# RiskChemi_Monitor_V1_03.net
KiCad netlist of a schematic drawn in Altium Designer
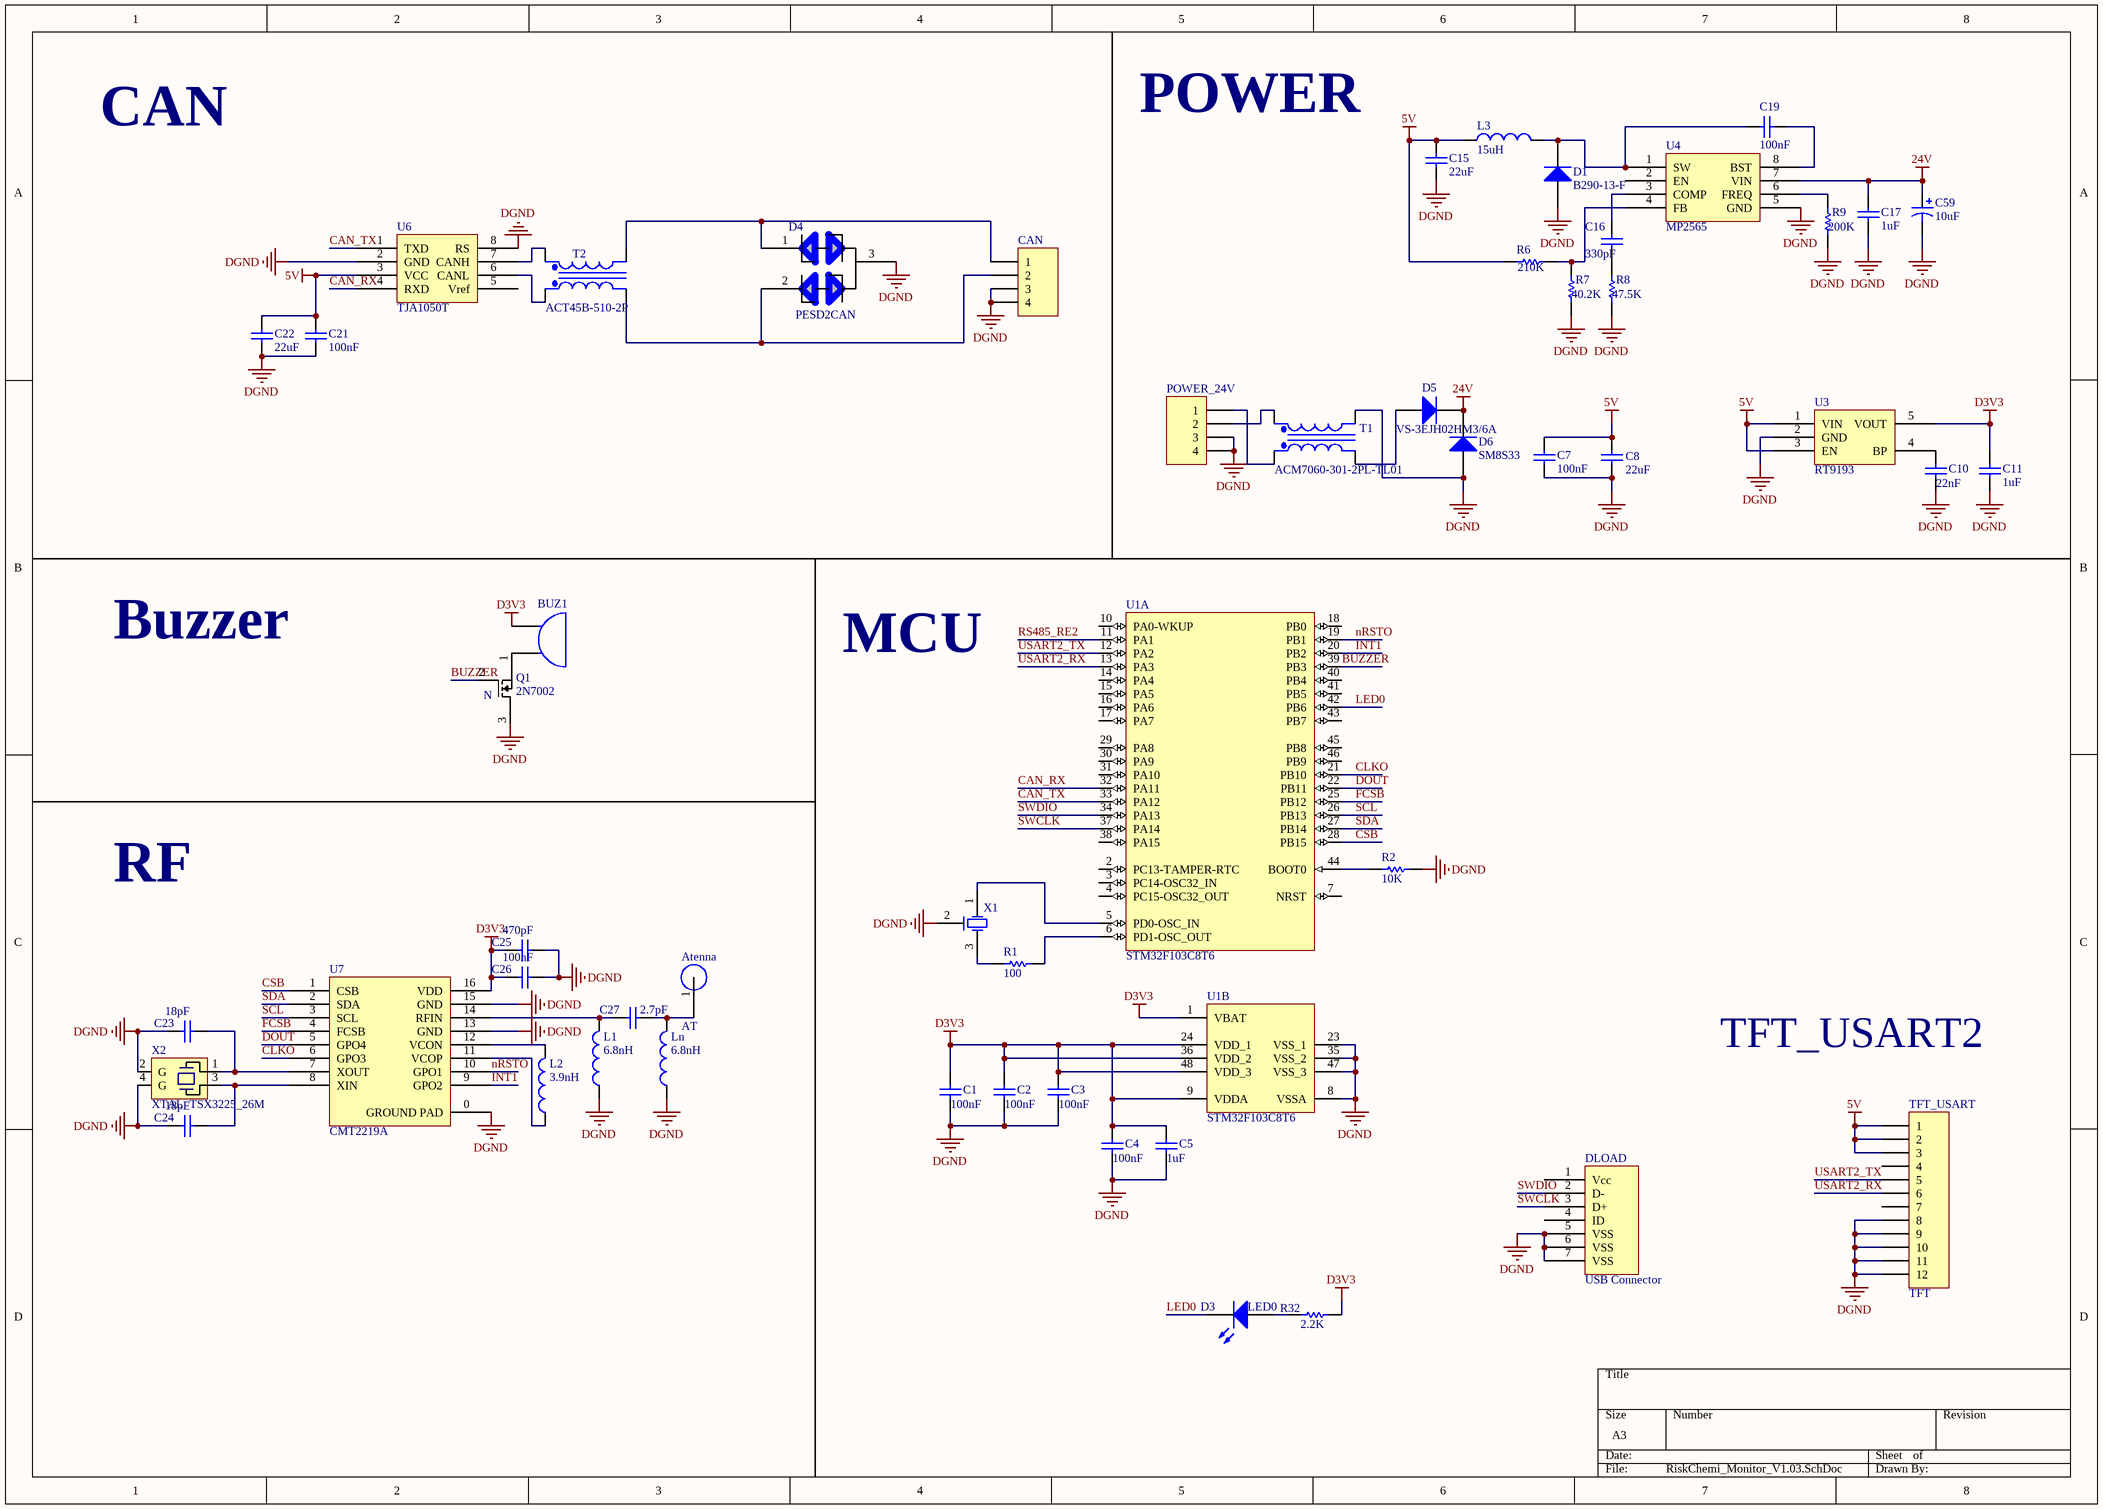
[diagram p0: RiskChemi_Monitor_V1.03.SchDoc]

(export (version "E")
  (design (tool "Eeschema 10.0.6"))
  (components
    (comp (ref "Atenna") (value "AT") (footprint "433MHz Atenna") (libsource (lib "MySchlib1") (part "AT")))
    (comp (ref "BUZ1")
      (value "BUZZER")
      (footprint "BUZ0905")
      (description "Buzzer")
      (libsource (lib "杂元件库") (part "BUZZER"))
    )
    (comp (ref "C1")
      (value "100nF")
      (footprint "0603")
      (description "Capacitor")
      (fields (field (name "PUBLISHER") "Altium Limited"))
      (libsource (lib "Miscellaneous Devices") (part "Cap"))
    )
    (comp (ref "C2")
      (value "100nF")
      (footprint "0603")
      (description "Capacitor")
      (fields (field (name "PUBLISHER") "Altium Limited"))
      (libsource (lib "Miscellaneous Devices") (part "Cap"))
    )
    (comp (ref "C3")
      (value "100nF")
      (footprint "0603")
      (description "Capacitor")
      (fields (field (name "PUBLISHER") "Altium Limited"))
      (libsource (lib "Miscellaneous Devices") (part "Cap"))
    )
    (comp (ref "C4")
      (value "100nF")
      (footprint "0603")
      (description "Capacitor")
      (fields (field (name "PUBLISHER") "Altium Limited"))
      (libsource (lib "Miscellaneous Devices") (part "Cap"))
    )
    (comp (ref "C5")
      (value "1uF")
      (footprint "0603")
      (description "Capacitor")
      (fields (field (name "PUBLISHER") "Altium Limited"))
      (libsource (lib "Miscellaneous Devices") (part "Cap"))
    )
    (comp (ref "C7")
      (value "100nF")
      (footprint "0805")
      (description "Capacitor,100V")
      (fields (field (name "PUBLISHER") "Altium Limited"))
      (libsource (lib "Miscellaneous Devices") (part "Cap"))
    )
    (comp (ref "C8")
      (value "22uF")
      (footprint "0805")
      (description "Capacitor")
      (fields (field (name "PUBLISHER") "Altium Limited"))
      (libsource (lib "Miscellaneous Devices") (part "Cap"))
    )
    (comp (ref "C10")
      (value "22nF")
      (footprint "BinFeng:0603")
      (description "Capacitor")
      (fields (field (name "PUBLISHER") "Altium Limited"))
      (libsource (lib "Miscellaneous Devices") (part "Cap"))
    )
    (comp (ref "C11")
      (value "1uF")
      (footprint "BinFeng:0603")
      (description "Capacitor")
      (fields (field (name "PUBLISHER") "Altium Limited"))
      (libsource (lib "Miscellaneous Devices") (part "Cap"))
    )
    (comp (ref "C15")
      (value "22uF")
      (footprint "0805")
      (description "Capacitor,50V")
      (fields (field (name "PUBLISHER") "Altium Limited"))
      (libsource (lib "Miscellaneous Devices") (part "Cap"))
    )
    (comp (ref "C16")
      (value "330pF")
      (footprint "BinFeng:0402")
      (description "Capacitor")
      (fields (field (name "PUBLISHER") "Altium Limited"))
      (libsource (lib "Miscellaneous Devices") (part "Cap"))
    )
    (comp (ref "C17")
      (value "1uF")
      (footprint "0805")
      (description "Capacitor,100V")
      (fields (field (name "PUBLISHER") "Altium Limited"))
      (libsource (lib "Miscellaneous Devices") (part "Cap"))
    )
    (comp (ref "C19")
      (value "100nF")
      (footprint "BinFeng:0402")
      (description "Capacitor")
      (fields (field (name "PUBLISHER") "Altium Limited"))
      (libsource (lib "Miscellaneous Devices") (part "Cap"))
    )
    (comp (ref "C21")
      (value "100nF")
      (footprint "0603")
      (description "Capacitor")
      (fields (field (name "PUBLISHER") "Altium Limited"))
      (libsource (lib "Miscellaneous Devices") (part "Cap"))
    )
    (comp (ref "C22")
      (value "22uF")
      (footprint "0805")
      (description "Capacitor")
      (fields (field (name "PUBLISHER") "Altium Limited"))
      (libsource (lib "Miscellaneous Devices") (part "Cap"))
    )
    (comp (ref "C23")
      (value "18pF")
      (footprint "BinFeng:0402")
      (description "Capacitor")
      (fields (field (name "PUBLISHER") "Altium Limited"))
      (libsource (lib "Miscellaneous Devices") (part "Cap"))
    )
    (comp (ref "C24")
      (value "18pF")
      (footprint "BinFeng:0402")
      (description "Capacitor")
      (fields (field (name "PUBLISHER") "Altium Limited"))
      (libsource (lib "Miscellaneous Devices") (part "Cap"))
    )
    (comp (ref "C25")
      (value "470pF")
      (footprint "BinFeng:0402")
      (description "Capacitor")
      (fields (field (name "PUBLISHER") "Altium Limited"))
      (libsource (lib "Miscellaneous Devices") (part "Cap"))
    )
    (comp (ref "C26")
      (value "100nF")
      (footprint "BinFeng:0603")
      (description "Capacitor")
      (fields (field (name "PUBLISHER") "Altium Limited"))
      (libsource (lib "Miscellaneous Devices") (part "Cap"))
    )
    (comp (ref "C27")
      (value "2.7pF")
      (footprint "BinFeng:nosilk_0402")
      (description "Capacitor")
      (fields (field (name "PUBLISHER") "Altium Limited"))
      (libsource (lib "Miscellaneous Devices") (part "Cap"))
    )
    (comp (ref "C59")
      (value "10uF")
      (footprint "6032_pol")
      (description "Polarized Capacitor (Radial)")
      (fields (field (name "PUBLISHER") "Altium Limited"))
      (libsource (lib "Miscellaneous Devices") (part "Cap Pol1"))
    )
    (comp (ref "CAN")
      (value "Header 4")
      (footprint "C3000VS")
      (description "Header, 4-Pin")
      (fields (field (name "PUBLISHER") "Altium Limited"))
      (libsource (lib "Miscellaneous Connectors") (part "Header 4"))
    )
    (comp (ref "D1")
      (value "B290-13-F")
      (footprint "back:B290")
      (description "Default Diode")
      (fields (field (name "PUBLISHER") "Altium Limited"))
      (libsource (lib "Miscellaneous Devices") (part "Diode"))
    )
    (comp (ref "D3")
      (value "LED0")
      (footprint "LED")
      (description "green LED")
      (fields (field (name "PUBLISHER") "Altium Limited"))
      (libsource (lib "Miscellaneous Devices") (part "LED0"))
    )
    (comp (ref "D4")
      (value "PESD2CAN")
      (footprint "SOT23")
      (libsource (lib "BinFeng_Connectors") (part "PESD1CAN"))
    )
    (comp (ref "D5")
      (value "VS-3EJH02HM3/6A")
      (footprint "back:B290")
      (description "1 Amp General Purpose Rectifier")
      (fields (field (name "PUBLISHER") "Altium Limited"))
      (libsource (lib "Miscellaneous Devices") (part "Diode 1N4007"))
    )
    (comp (ref "D6")
      (value "SM8S33")
      (footprint "SM8S")
      (description "1 Amp General Purpose Rectifier")
      (fields (field (name "PUBLISHER") "Altium Limited"))
      (libsource (lib "Miscellaneous Devices") (part "Diode 1N4007"))
    )
    (comp (ref "DLOAD")
      (value "USB Connector")
      (footprint "Mini_USB")
      (libsource (lib "BinFeng_Connectors") (part "Component_1"))
    )
    (comp (ref "L1")
      (value "6.8nH")
      (footprint "Miscellaneous Devices:0402")
      (description "Inductor")
      (fields (field (name "PUBLISHER") "Altium Limited"))
      (libsource (lib "Miscellaneous Devices") (part "Inductor"))
    )
    (comp (ref "L2")
      (value "3.9nH")
      (footprint "BinFeng:0603")
      (description "Inductor")
      (fields (field (name "PUBLISHER") "Altium Limited"))
      (libsource (lib "Miscellaneous Devices") (part "Inductor"))
    )
    (comp (ref "L3")
      (value "15uH")
      (footprint "4*4 Inductor")
      (description "Inductor, 1A")
      (fields (field (name "PUBLISHER") "Altium Limited"))
      (libsource (lib "Miscellaneous Devices") (part "Inductor"))
    )
    (comp (ref "Ln")
      (value "6.8nH")
      (footprint "Miscellaneous Devices:0402")
      (description "Inductor")
      (fields (field (name "PUBLISHER") "Altium Limited"))
      (libsource (lib "Miscellaneous Devices") (part "Inductor"))
    )
    (comp (ref "POWER_24V")
      (value "Header 4")
      (footprint "C3000VS")
      (description "Header, 4-Pin")
      (fields (field (name "PUBLISHER") "Altium Limited"))
      (libsource (lib "") (part "Header 4_1"))
    )
    (comp (ref "Q1") (value "2N7002") (footprint "2N7002") (libsource (lib "seeder") (part "N-MOSFET")))
    (comp (ref "R1")
      (value "100")
      (footprint "back:0603")
      (description "Resistor")
      (fields (field (name "PUBLISHER") "Altium Limited"))
      (libsource (lib "Miscellaneous Devices") (part "Res1"))
    )
    (comp (ref "R2")
      (value "10K")
      (footprint "back:0603")
      (description "Resistor")
      (fields (field (name "PUBLISHER") "Altium Limited"))
      (libsource (lib "Miscellaneous Devices") (part "Res1"))
    )
    (comp (ref "R6")
      (value "210K")
      (footprint "BinFeng:0402")
      (description "Resistor")
      (fields (field (name "PUBLISHER") "Altium Limited"))
      (libsource (lib "Miscellaneous Devices") (part "Res1"))
    )
    (comp (ref "R7")
      (value "40.2K")
      (footprint "BinFeng:0402")
      (description "Resistor")
      (fields (field (name "PUBLISHER") "Altium Limited"))
      (libsource (lib "Miscellaneous Devices") (part "Res1"))
    )
    (comp (ref "R8")
      (value "47.5K")
      (footprint "BinFeng:0402")
      (description "Resistor")
      (fields (field (name "PUBLISHER") "Altium Limited"))
      (libsource (lib "Miscellaneous Devices") (part "Res1"))
    )
    (comp (ref "R9")
      (value "200K")
      (footprint "BinFeng:0402")
      (description "Resistor")
      (fields (field (name "PUBLISHER") "Altium Limited"))
      (libsource (lib "Miscellaneous Devices") (part "Res1"))
    )
    (comp (ref "R32")
      (value "2.2K")
      (footprint "BinFeng:0603")
      (description "Resistor")
      (fields (field (name "PUBLISHER") "Altium Limited"))
      (libsource (lib "Miscellaneous Devices") (part "Res1"))
    )
    (comp (ref "T1")
      (value "ACM7060-301-2PL-TL01")
      (footprint "ACM7060-301-2P-TL01")
      (description "Transformer (Equivalent Circuit Model)")
      (fields (field (name "PUBLISHER") "Altium Limited"))
      (libsource (lib "Miscellaneous Devices") (part "Trans Eq"))
    )
    (comp (ref "T2")
      (value "ACT45B-510-2P")
      (footprint "ACT45B-510-2P")
      (description "Transformer (Equivalent Circuit Model)")
      (fields (field (name "PUBLISHER") "Altium Limited"))
      (libsource (lib "Miscellaneous Devices") (part "Trans Eq"))
    )
    (comp (ref "TFT_USART")
      (value "TFT")
      (footprint "FCC_10pin_1mm")
      (description "Header, 12-Pin")
      (fields (field (name "PUBLISHER") "Altium Limited"))
      (libsource (lib "Miscellaneous Connectors") (part "Header 12"))
    )
    (comp (ref "U1")
      (value "STM32F103C8T6")
      (footprint "STM-LQFP48_M")
      (libsource (lib "STMicroelectronics STM32 F1") (part "STM32F103C8T6"))
    )
    (comp (ref "U3") (value "RT9193") (footprint "SOT-23-5") (libsource (lib "BinFeng_IC") (part "RT9193")))
    (comp (ref "U4")
      (value "MP2565")
      (footprint "SO8")
      (description "DCDC 4.5V~28V input 1.8V ~5V output low power")
      (libsource (lib "BinFeng_IC") (part "MP1584"))
    )
    (comp (ref "U6")
      (value "TJA1050T")
      (footprint "SO8")
      (description "CAN Tranceiver")
      (libsource (lib "BinFeng_IC") (part "TJA1050T"))
    )
    (comp (ref "U7")
      (value "CMT2219A")
      (footprint "back:QFN16")
      (libsource (lib "BinFeng_IC") (part "CMT2219A"))
    )
    (comp (ref "X1") (value "8M smd") (footprint "8Mhz_XTAL") (libsource (lib "Schlib1") (part "8M smd")))
    (comp (ref "X2")
      (value "XTAL_TSX3225_26M")
      (footprint "XTAL3225")
      (libsource (lib "BinFeng_IC") (part "XTAL_Negative"))
    )
  )
  (nets
    (net (code "1") (name "/BUZZER") (class "Default")
      (node (ref "Q1") (pin "2") (pinfunction "G_2") (pintype "passive"))
      (node (ref "U1") (pin "39") (pinfunction "PB3_39") (pintype "bidirectional"))
    )
    (net (code "2") (name "/CAN_RX") (class "Default")
      (node (ref "U1") (pin "32") (pinfunction "PA11_32") (pintype "bidirectional"))
      (node (ref "U6") (pin "4") (pinfunction "RXD_4") (pintype "passive"))
    )
    (net (code "3") (name "/CAN_TX") (class "Default")
      (node (ref "U1") (pin "33") (pinfunction "PA12_33") (pintype "bidirectional"))
      (node (ref "U6") (pin "1") (pinfunction "TXD_1") (pintype "passive"))
    )
    (net (code "4") (name "/CLKO") (class "Default")
      (node (ref "U1") (pin "21") (pinfunction "PB10_21") (pintype "bidirectional"))
      (node (ref "U7") (pin "6") (pinfunction "GPO3_6") (pintype "passive"))
    )
    (net (code "5") (name "/CSB") (class "Default")
      (node (ref "U1") (pin "28") (pinfunction "PB15_28") (pintype "bidirectional"))
      (node (ref "U7") (pin "1") (pinfunction "CSB_1") (pintype "passive"))
    )
    (net (code "6") (name "/DOUT") (class "Default")
      (node (ref "U1") (pin "22") (pinfunction "PB11_22") (pintype "bidirectional"))
      (node (ref "U7") (pin "5") (pinfunction "GPO4_5") (pintype "passive"))
    )
    (net (code "7") (name "/FCSB") (class "Default")
      (node (ref "U1") (pin "25") (pinfunction "PB12_25") (pintype "bidirectional"))
      (node (ref "U7") (pin "4") (pinfunction "FCSB_4") (pintype "passive"))
    )
    (net (code "8") (name "/INT1") (class "Default")
      (node (ref "U1") (pin "20") (pinfunction "PB2_20") (pintype "bidirectional"))
      (node (ref "U7") (pin "9") (pinfunction "GPO2_9") (pintype "passive"))
    )
    (net (code "9") (name "/LED0") (class "Default")
      (node (ref "D3") (pin "2") (pinfunction "K_2") (pintype "passive"))
      (node (ref "U1") (pin "42") (pinfunction "PB6_42") (pintype "bidirectional"))
    )
    (net (code "10") (name "/RS485_RE2") (class "Default")
      (node (ref "U1") (pin "11") (pinfunction "PA1_11") (pintype "bidirectional"))
    )
    (net (code "11") (name "/SCL") (class "Default")
      (node (ref "U1") (pin "26") (pinfunction "PB13_26") (pintype "bidirectional"))
      (node (ref "U7") (pin "3") (pinfunction "SCL_3") (pintype "passive"))
    )
    (net (code "12") (name "/SDA") (class "Default")
      (node (ref "U1") (pin "27") (pinfunction "PB14_27") (pintype "bidirectional"))
      (node (ref "U7") (pin "2") (pinfunction "SDA_2") (pintype "passive"))
    )
    (net (code "13") (name "/SWCLK") (class "Default")
      (node (ref "DLOAD") (pin "3") (pinfunction "D+_3") (pintype "passive"))
      (node (ref "U1") (pin "37") (pinfunction "PA14_37") (pintype "bidirectional"))
    )
    (net (code "14") (name "/SWDIO") (class "Default")
      (node (ref "DLOAD") (pin "2") (pinfunction "D-_2") (pintype "passive"))
      (node (ref "U1") (pin "34") (pinfunction "PA13_34") (pintype "bidirectional"))
    )
    (net (code "15") (name "/USART2_RX") (class "Default")
      (node (ref "TFT_USART") (pin "6") (pinfunction "6_6") (pintype "passive"))
      (node (ref "U1") (pin "13") (pinfunction "PA3_13") (pintype "bidirectional"))
    )
    (net (code "16") (name "/USART2_TX") (class "Default")
      (node (ref "TFT_USART") (pin "5") (pinfunction "5_5") (pintype "passive"))
      (node (ref "U1") (pin "12") (pinfunction "PA2_12") (pintype "bidirectional"))
    )
    (net (code "17") (name "/nRSTO") (class "Default")
      (node (ref "U1") (pin "19") (pinfunction "PB1_19") (pintype "bidirectional"))
      (node (ref "U7") (pin "10") (pinfunction "GPO1_10") (pintype "passive"))
    )
    (net (code "18") (name "5V") (class "Default")
      (node (ref "C15") (pin "2") (pinfunction "2_2") (pintype "passive"))
      (node (ref "C21") (pin "1") (pinfunction "1_1") (pintype "passive"))
      (node (ref "C22") (pin "2") (pinfunction "2_2") (pintype "passive"))
      (node (ref "C7") (pin "2") (pinfunction "2_2") (pintype "passive"))
      (node (ref "C8") (pin "2") (pinfunction "2_2") (pintype "passive"))
      (node (ref "L3") (pin "1") (pinfunction "1_1") (pintype "passive"))
      (node (ref "R6") (pin "2") (pinfunction "2_2") (pintype "passive"))
      (node (ref "TFT_USART") (pin "1") (pinfunction "1_1") (pintype "passive"))
      (node (ref "TFT_USART") (pin "2") (pinfunction "2_2") (pintype "passive"))
      (node (ref "TFT_USART") (pin "3") (pinfunction "3_3") (pintype "passive"))
      (node (ref "U3") (pin "1") (pinfunction "VIN_1") (pintype "passive"))
      (node (ref "U3") (pin "3") (pinfunction "EN_3") (pintype "passive"))
      (node (ref "U6") (pin "3") (pinfunction "VCC_3") (pintype "passive"))
    )
    (net (code "19") (name "24V") (class "Default")
      (node (ref "C17") (pin "2") (pinfunction "2_2") (pintype "passive"))
      (node (ref "C59") (pin "1") (pinfunction "1_1") (pintype "passive"))
      (node (ref "D5") (pin "2") (pinfunction "K_2") (pintype "passive"))
      (node (ref "D6") (pin "2") (pinfunction "K_2") (pintype "passive"))
      (node (ref "U4") (pin "7") (pinfunction "VIN_7") (pintype "passive"))
    )
    (net (code "20") (name "D3V3") (class "Default")
      (node (ref "BUZ1") (pin "1") (pinfunction "A_1") (pintype "passive"))
      (node (ref "C1") (pin "2") (pinfunction "2_2") (pintype "passive"))
      (node (ref "C11") (pin "2") (pinfunction "2_2") (pintype "passive"))
      (node (ref "C2") (pin "2") (pinfunction "2_2") (pintype "passive"))
      (node (ref "C25") (pin "2") (pinfunction "2_2") (pintype "passive"))
      (node (ref "C26") (pin "2") (pinfunction "2_2") (pintype "passive"))
      (node (ref "C3") (pin "2") (pinfunction "2_2") (pintype "passive"))
      (node (ref "C4") (pin "2") (pinfunction "2_2") (pintype "passive"))
      (node (ref "C5") (pin "2") (pinfunction "2_2") (pintype "passive"))
      (node (ref "R32") (pin "1") (pinfunction "1_1") (pintype "passive"))
      (node (ref "U1") (pin "1") (pinfunction "VBAT_1") (pintype "power_in"))
      (node (ref "U1") (pin "24") (pinfunction "VDD_1_24") (pintype "power_in"))
      (node (ref "U1") (pin "36") (pinfunction "VDD_2_36") (pintype "power_in"))
      (node (ref "U1") (pin "48") (pinfunction "VDD_3_48") (pintype "power_in"))
      (node (ref "U1") (pin "9") (pinfunction "VDDA_9") (pintype "power_in"))
      (node (ref "U3") (pin "5") (pinfunction "VOUT_5") (pintype "passive"))
      (node (ref "U7") (pin "16") (pinfunction "VDD_16") (pintype "passive"))
    )
    (net (code "21") (name "DGND") (class "Default")
      (node (ref "C1") (pin "1") (pinfunction "1_1") (pintype "passive"))
      (node (ref "C10") (pin "1") (pinfunction "1_1") (pintype "passive"))
      (node (ref "C11") (pin "1") (pinfunction "1_1") (pintype "passive"))
      (node (ref "C15") (pin "1") (pinfunction "1_1") (pintype "passive"))
      (node (ref "C17") (pin "1") (pinfunction "1_1") (pintype "passive"))
      (node (ref "C2") (pin "1") (pinfunction "1_1") (pintype "passive"))
      (node (ref "C21") (pin "2") (pinfunction "2_2") (pintype "passive"))
      (node (ref "C22") (pin "1") (pinfunction "1_1") (pintype "passive"))
      (node (ref "C23") (pin "2") (pinfunction "2_2") (pintype "passive"))
      (node (ref "C24") (pin "2") (pinfunction "2_2") (pintype "passive"))
      (node (ref "C25") (pin "1") (pinfunction "1_1") (pintype "passive"))
      (node (ref "C26") (pin "1") (pinfunction "1_1") (pintype "passive"))
      (node (ref "C3") (pin "1") (pinfunction "1_1") (pintype "passive"))
      (node (ref "C4") (pin "1") (pinfunction "1_1") (pintype "passive"))
      (node (ref "C5") (pin "1") (pinfunction "1_1") (pintype "passive"))
      (node (ref "C59") (pin "2") (pinfunction "2_2") (pintype "passive"))
      (node (ref "C7") (pin "1") (pinfunction "1_1") (pintype "passive"))
      (node (ref "C8") (pin "1") (pinfunction "1_1") (pintype "passive"))
      (node (ref "CAN") (pin "3") (pinfunction "3_3") (pintype "passive"))
      (node (ref "CAN") (pin "4") (pinfunction "4_4") (pintype "passive"))
      (node (ref "D1") (pin "1") (pinfunction "A_1") (pintype "passive"))
      (node (ref "D4") (pin "3") (pinfunction "13_3") (pintype "passive"))
      (node (ref "D6") (pin "1") (pinfunction "A_1") (pintype "passive"))
      (node (ref "DLOAD") (pin "5") (pinfunction "VSS_5") (pintype "passive"))
      (node (ref "DLOAD") (pin "6") (pinfunction "VSS_6") (pintype "passive"))
      (node (ref "DLOAD") (pin "7") (pinfunction "VSS_7") (pintype "passive"))
      (node (ref "L1") (pin "1") (pinfunction "1_1") (pintype "passive"))
      (node (ref "Ln") (pin "1") (pinfunction "1_1") (pintype "passive"))
      (node (ref "POWER_24V") (pin "3") (pinfunction "3_3") (pintype "passive"))
      (node (ref "POWER_24V") (pin "4") (pinfunction "4_4") (pintype "passive"))
      (node (ref "Q1") (pin "3") (pinfunction "S_3") (pintype "passive"))
      (node (ref "R2") (pin "2") (pinfunction "2_2") (pintype "passive"))
      (node (ref "R7") (pin "1") (pinfunction "1_1") (pintype "passive"))
      (node (ref "R8") (pin "1") (pinfunction "1_1") (pintype "passive"))
      (node (ref "R9") (pin "1") (pinfunction "1_1") (pintype "passive"))
      (node (ref "T1") (pin "4") (pinfunction "Sec-_4") (pintype "passive"))
      (node (ref "TFT_USART") (pin "10") (pinfunction "10_10") (pintype "passive"))
      (node (ref "TFT_USART") (pin "11") (pinfunction "11_11") (pintype "passive"))
      (node (ref "TFT_USART") (pin "12") (pinfunction "12_12") (pintype "passive"))
      (node (ref "TFT_USART") (pin "8") (pinfunction "8_8") (pintype "passive"))
      (node (ref "TFT_USART") (pin "9") (pinfunction "9_9") (pintype "passive"))
      (node (ref "U1") (pin "23") (pinfunction "VSS_1_23") (pintype "power_in"))
      (node (ref "U1") (pin "35") (pinfunction "VSS_2_35") (pintype "power_in"))
      (node (ref "U1") (pin "47") (pinfunction "VSS_3_47") (pintype "power_in"))
      (node (ref "U1") (pin "8") (pinfunction "VSSA_8") (pintype "power_in"))
      (node (ref "U3") (pin "2") (pinfunction "GND_2") (pintype "passive"))
      (node (ref "U4") (pin "5") (pinfunction "GND_5") (pintype "passive"))
      (node (ref "U6") (pin "2") (pinfunction "GND_2") (pintype "passive"))
      (node (ref "U6") (pin "8") (pinfunction "RS_8") (pintype "passive"))
      (node (ref "U7") (pin "0") (pinfunction "GROUND_PAD_0") (pintype "passive"))
      (node (ref "U7") (pin "13") (pinfunction "GND_13") (pintype "passive"))
      (node (ref "U7") (pin "15") (pinfunction "GND_15") (pintype "passive"))
      (node (ref "X1") (pin "2") (pinfunction "GND_2") (pintype "passive"))
      (node (ref "X2") (pin "2") (pinfunction "G_2") (pintype "passive"))
      (node (ref "X2") (pin "4") (pinfunction "G_4") (pintype "passive"))
    )
    (net (code "22") (name "Net-(Atenna-Pad1)") (class "Default")
      (node (ref "Atenna") (pin "1") (pinfunction "1_1") (pintype "passive"))
      (node (ref "C27") (pin "1") (pinfunction "1_1") (pintype "passive"))
      (node (ref "Ln") (pin "2") (pinfunction "2_2") (pintype "passive"))
    )
    (net (code "23") (name "Net-(BUZ1-B)") (class "Default")
      (node (ref "BUZ1") (pin "2") (pinfunction "B_2") (pintype "passive"))
      (node (ref "Q1") (pin "1") (pinfunction "D_1") (pintype "passive"))
    )
    (net (code "24") (name "Net-(C16-Pad2)") (class "Default")
      (node (ref "C16") (pin "2") (pinfunction "2_2") (pintype "passive"))
      (node (ref "R8") (pin "2") (pinfunction "2_2") (pintype "passive"))
    )
    (net (code "25") (name "Net-(D1-K)") (class "Default")
      (node (ref "C19") (pin "2") (pinfunction "2_2") (pintype "passive"))
      (node (ref "D1") (pin "2") (pinfunction "K_2") (pintype "passive"))
      (node (ref "L3") (pin "2") (pinfunction "2_2") (pintype "passive"))
      (node (ref "U4") (pin "1") (pinfunction "SW_1") (pintype "passive"))
    )
    (net (code "26") (name "Net-(D3-A)") (class "Default")
      (node (ref "D3") (pin "1") (pinfunction "A_1") (pintype "passive"))
      (node (ref "R32") (pin "2") (pinfunction "2_2") (pintype "passive"))
    )
    (net (code "27") (name "Net-(D4-11)") (class "Default")
      (node (ref "CAN") (pin "1") (pinfunction "1_1") (pintype "passive"))
      (node (ref "D4") (pin "1") (pinfunction "11_1") (pintype "passive"))
      (node (ref "T2") (pin "4") (pinfunction "Sec-_4") (pintype "passive"))
    )
    (net (code "28") (name "Net-(D4-12)") (class "Default")
      (node (ref "CAN") (pin "2") (pinfunction "2_2") (pintype "passive"))
      (node (ref "D4") (pin "2") (pinfunction "12_2") (pintype "passive"))
      (node (ref "T2") (pin "2") (pinfunction "Pri-_2") (pintype "passive"))
    )
    (net (code "29") (name "Net-(D5-A)") (class "Default")
      (node (ref "D5") (pin "1") (pinfunction "A_1") (pintype "passive"))
      (node (ref "T1") (pin "2") (pinfunction "Pri-_2") (pintype "passive"))
    )
    (net (code "30") (name "Net-(T1-Pri+)") (class "Default")
      (node (ref "POWER_24V") (pin "1") (pinfunction "1_1") (pintype "passive"))
      (node (ref "T1") (pin "1") (pinfunction "Pri+_1") (pintype "passive"))
    )
    (net (code "31") (name "Net-(T1-Sec+)") (class "Default")
      (node (ref "POWER_24V") (pin "2") (pinfunction "2_2") (pintype "passive"))
      (node (ref "T1") (pin "3") (pinfunction "Sec+_3") (pintype "passive"))
    )
    (net (code "32") (name "Net-(T2-Pri+)") (class "Default")
      (node (ref "T2") (pin "1") (pinfunction "Pri+_1") (pintype "passive"))
      (node (ref "U6") (pin "6") (pinfunction "CANL_6") (pintype "passive"))
    )
    (net (code "33") (name "Net-(T2-Sec+)") (class "Default")
      (node (ref "T2") (pin "3") (pinfunction "Sec+_3") (pintype "passive"))
      (node (ref "U6") (pin "7") (pinfunction "CANH_7") (pintype "passive"))
    )
    (net (code "34") (name "Net-(U1A-BOOT0)") (class "Default")
      (node (ref "R2") (pin "1") (pinfunction "1_1") (pintype "passive"))
      (node (ref "U1") (pin "44") (pinfunction "BOOT0_44") (pintype "input"))
    )
    (net (code "35") (name "Net-(U1A-PD0-OSC_IN)") (class "Default")
      (node (ref "U1") (pin "5") (pinfunction "PD0-OSC_IN_5") (pintype "bidirectional"))
      (node (ref "X1") (pin "1") (pinfunction "OSC1_1") (pintype "passive"))
    )
    (net (code "36") (name "Net-(U1A-PD1-OSC_OUT)") (class "Default")
      (node (ref "R1") (pin "2") (pinfunction "2_2") (pintype "passive"))
      (node (ref "U1") (pin "6") (pinfunction "PD1-OSC_OUT_6") (pintype "bidirectional"))
    )
    (net (code "37") (name "Net-(U3-BP)") (class "Default")
      (node (ref "C10") (pin "2") (pinfunction "2_2") (pintype "passive"))
      (node (ref "U3") (pin "4") (pinfunction "BP_4") (pintype "passive"))
    )
    (net (code "38") (name "Net-(U4-BST)") (class "Default")
      (node (ref "C19") (pin "1") (pinfunction "1_1") (pintype "passive"))
      (node (ref "U4") (pin "8") (pinfunction "BST_8") (pintype "passive"))
    )
    (net (code "39") (name "Net-(U4-COMP)") (class "Default")
      (node (ref "C16") (pin "1") (pinfunction "1_1") (pintype "passive"))
      (node (ref "U4") (pin "3") (pinfunction "COMP_3") (pintype "passive"))
    )
    (net (code "40") (name "Net-(U4-FB)") (class "Default")
      (node (ref "R6") (pin "1") (pinfunction "1_1") (pintype "passive"))
      (node (ref "R7") (pin "2") (pinfunction "2_2") (pintype "passive"))
      (node (ref "U4") (pin "4") (pinfunction "FB_4") (pintype "passive"))
    )
    (net (code "41") (name "Net-(U4-FREQ)") (class "Default")
      (node (ref "R9") (pin "2") (pinfunction "2_2") (pintype "passive"))
      (node (ref "U4") (pin "6") (pinfunction "FREQ_6") (pintype "passive"))
    )
    (net (code "42") (name "Net-(U7-RFIN)") (class "Default")
      (node (ref "C27") (pin "2") (pinfunction "2_2") (pintype "passive"))
      (node (ref "L1") (pin "2") (pinfunction "2_2") (pintype "passive"))
      (node (ref "U7") (pin "14") (pinfunction "RFIN_14") (pintype "passive"))
    )
    (net (code "43") (name "Net-(U7-VCON)") (class "Default")
      (node (ref "L2") (pin "2") (pinfunction "2_2") (pintype "passive"))
      (node (ref "U7") (pin "12") (pinfunction "VCON_12") (pintype "passive"))
    )
    (net (code "44") (name "Net-(U7-VCOP)") (class "Default")
      (node (ref "L2") (pin "1") (pinfunction "1_1") (pintype "passive"))
      (node (ref "U7") (pin "11") (pinfunction "VCOP_11") (pintype "passive"))
    )
    (net (code "45") (name "Net-(U7-XIN)") (class "Default")
      (node (ref "C24") (pin "1") (pinfunction "1_1") (pintype "passive"))
      (node (ref "U7") (pin "8") (pinfunction "XIN_8") (pintype "passive"))
      (node (ref "X2") (pin "3") (pintype "passive"))
    )
    (net (code "46") (name "Net-(U7-XOUT)") (class "Default")
      (node (ref "C23") (pin "1") (pinfunction "1_1") (pintype "passive"))
      (node (ref "U7") (pin "7") (pinfunction "XOUT_7") (pintype "passive"))
      (node (ref "X2") (pin "1") (pintype "passive"))
    )
    (net (code "47") (name "Net-(X1-OSC2)") (class "Default")
      (node (ref "R1") (pin "1") (pinfunction "1_1") (pintype "passive"))
      (node (ref "X1") (pin "3") (pinfunction "OSC2_3") (pintype "passive"))
    )
    (net (code "48") (name "unconnected-(DLOAD-ID-Pad4)") (class "Default")
      (node (ref "DLOAD") (pin "4") (pinfunction "ID_4") (pintype "passive"))
    )
    (net (code "49") (name "unconnected-(DLOAD-Vcc-Pad1)") (class "Default")
      (node (ref "DLOAD") (pin "1") (pinfunction "Vcc_1") (pintype "passive"))
    )
    (net (code "50") (name "unconnected-(TFT_USART-Pad4)") (class "Default")
      (node (ref "TFT_USART") (pin "4") (pinfunction "4_4") (pintype "passive"))
    )
    (net (code "51") (name "unconnected-(TFT_USART-Pad7)") (class "Default")
      (node (ref "TFT_USART") (pin "7") (pinfunction "7_7") (pintype "passive"))
    )
    (net (code "52") (name "unconnected-(U1A-NRST-Pad7)") (class "Default")
      (node (ref "U1") (pin "7") (pinfunction "NRST_7") (pintype "bidirectional"))
    )
    (net (code "53") (name "unconnected-(U1A-PA0-WKUP-Pad10)") (class "Default")
      (node (ref "U1") (pin "10") (pinfunction "PA0-WKUP_10") (pintype "bidirectional"))
    )
    (net (code "54") (name "unconnected-(U1A-PA4-Pad14)") (class "Default")
      (node (ref "U1") (pin "14") (pinfunction "PA4_14") (pintype "bidirectional"))
    )
    (net (code "55") (name "unconnected-(U1A-PA5-Pad15)") (class "Default")
      (node (ref "U1") (pin "15") (pinfunction "PA5_15") (pintype "bidirectional"))
    )
    (net (code "56") (name "unconnected-(U1A-PA6-Pad16)") (class "Default")
      (node (ref "U1") (pin "16") (pinfunction "PA6_16") (pintype "bidirectional"))
    )
    (net (code "57") (name "unconnected-(U1A-PA7-Pad17)") (class "Default")
      (node (ref "U1") (pin "17") (pinfunction "PA7_17") (pintype "bidirectional"))
    )
    (net (code "58") (name "unconnected-(U1A-PA8-Pad29)") (class "Default")
      (node (ref "U1") (pin "29") (pinfunction "PA8_29") (pintype "bidirectional"))
    )
    (net (code "59") (name "unconnected-(U1A-PA9-Pad30)") (class "Default")
      (node (ref "U1") (pin "30") (pinfunction "PA9_30") (pintype "bidirectional"))
    )
    (net (code "60") (name "unconnected-(U1A-PA10-Pad31)") (class "Default")
      (node (ref "U1") (pin "31") (pinfunction "PA10_31") (pintype "bidirectional"))
    )
    (net (code "61") (name "unconnected-(U1A-PA15-Pad38)") (class "Default")
      (node (ref "U1") (pin "38") (pinfunction "PA15_38") (pintype "bidirectional"))
    )
    (net (code "62") (name "unconnected-(U1A-PB0-Pad18)") (class "Default")
      (node (ref "U1") (pin "18") (pinfunction "PB0_18") (pintype "bidirectional"))
    )
    (net (code "63") (name "unconnected-(U1A-PB4-Pad40)") (class "Default")
      (node (ref "U1") (pin "40") (pinfunction "PB4_40") (pintype "bidirectional"))
    )
    (net (code "64") (name "unconnected-(U1A-PB5-Pad41)") (class "Default")
      (node (ref "U1") (pin "41") (pinfunction "PB5_41") (pintype "bidirectional"))
    )
    (net (code "65") (name "unconnected-(U1A-PB7-Pad43)") (class "Default")
      (node (ref "U1") (pin "43") (pinfunction "PB7_43") (pintype "bidirectional"))
    )
    (net (code "66") (name "unconnected-(U1A-PB8-Pad45)") (class "Default")
      (node (ref "U1") (pin "45") (pinfunction "PB8_45") (pintype "bidirectional"))
    )
    (net (code "67") (name "unconnected-(U1A-PB9-Pad46)") (class "Default")
      (node (ref "U1") (pin "46") (pinfunction "PB9_46") (pintype "bidirectional"))
    )
    (net (code "68") (name "unconnected-(U1A-PC13-TAMPER-RTC-Pad2)") (class "Default")
      (node (ref "U1") (pin "2") (pinfunction "PC13-TAMPER-RTC_2") (pintype "bidirectional"))
    )
    (net (code "69") (name "unconnected-(U1A-PC14-OSC32_IN-Pad3)") (class "Default")
      (node (ref "U1") (pin "3") (pinfunction "PC14-OSC32_IN_3") (pintype "bidirectional"))
    )
    (net (code "70") (name "unconnected-(U1A-PC15-OSC32_OUT-Pad4)") (class "Default")
      (node (ref "U1") (pin "4") (pinfunction "PC15-OSC32_OUT_4") (pintype "bidirectional"))
    )
    (net (code "71") (name "unconnected-(U4-EN-Pad2)") (class "Default")
      (node (ref "U4") (pin "2") (pinfunction "EN_2") (pintype "passive"))
    )
    (net (code "72") (name "unconnected-(U6-Vref-Pad5)") (class "Default")
      (node (ref "U6") (pin "5") (pinfunction "Vref_5") (pintype "passive"))
    )
  )
)
